# Sheet.net
KiCad netlist of a schematic drawn in Altium Designer
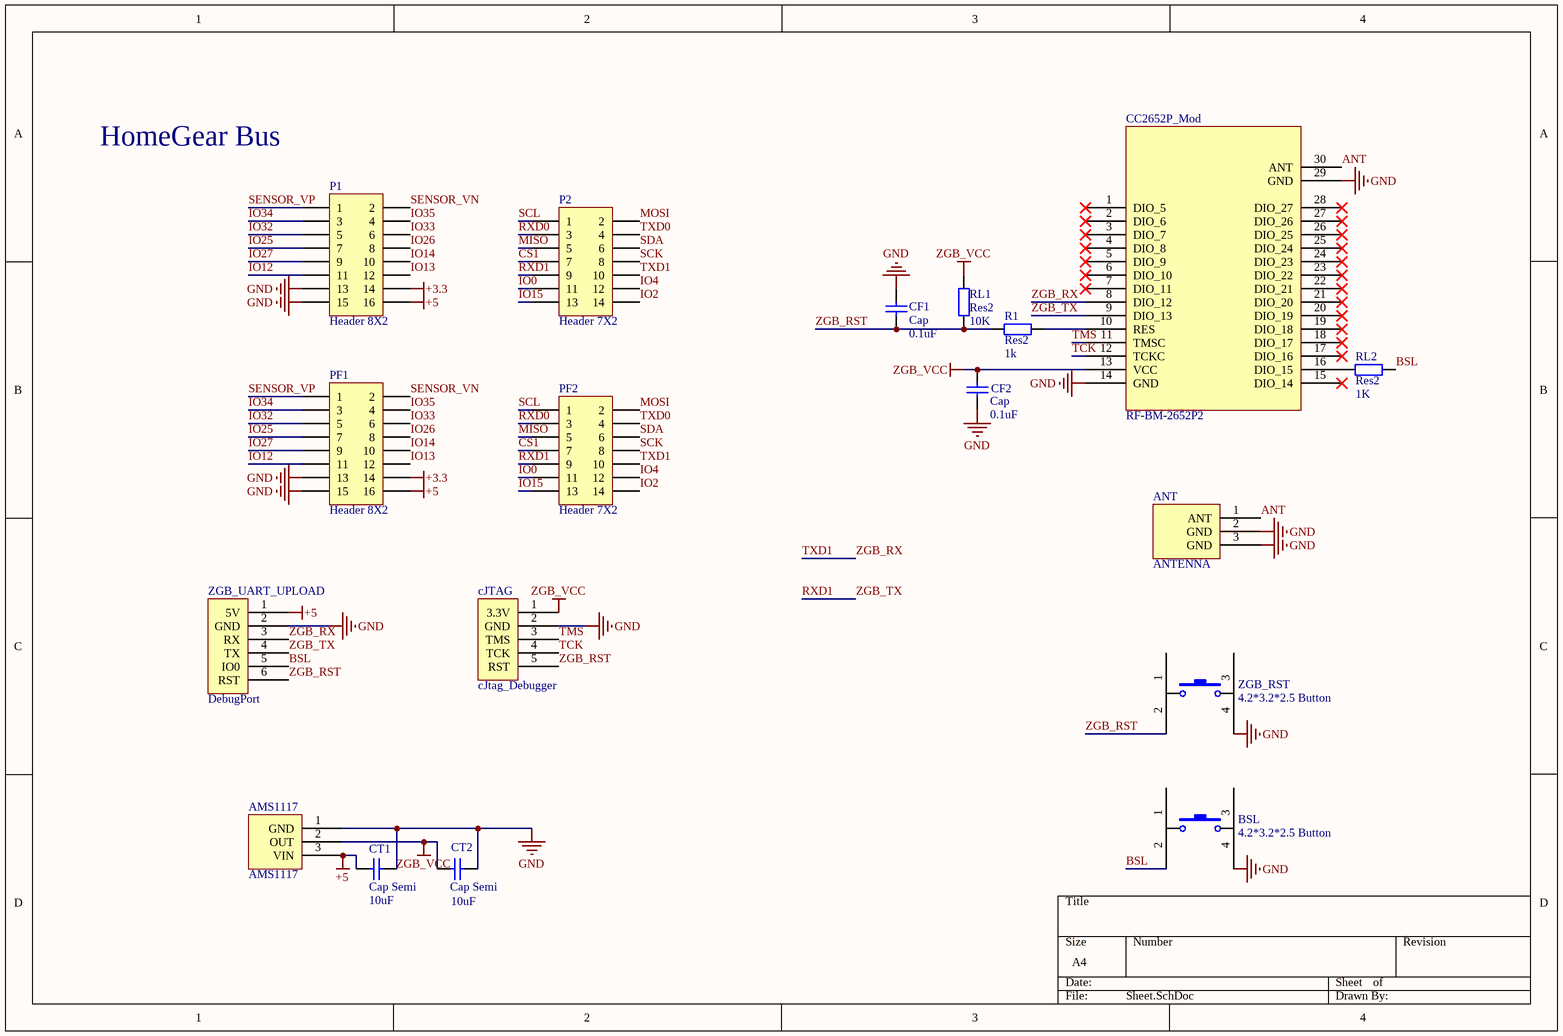
[diagram p0: Sheet.SchDoc]

(export (version "E")
  (design (tool "Eeschema 10.0.6"))
  (components
    (comp (ref "AMS1117")
      (value "AMS1117")
      (footprint "SOT-223-2")
      (libsource (lib "Schlib2") (part "AMS1117"))
    )
    (comp (ref "ANT") (value "ANTENNA") (footprint "SMA-2") (libsource (lib "我的元件库") (part "ANTENNA")))
    (comp (ref "BSL")
      (value "4.2*3.2*2.5 Button")
      (footprint "TSW 4.2*3.2*2.5")
      (libsource (lib "我的元件库") (part "4.2*3.2*2.5 Button"))
    )
    (comp (ref "CC2652P_Mod")
      (value "RF-BM-2652P2")
      (footprint "RF-BM-2652P2")
      (libsource (lib "我的元件库") (part "RF-BM-2652P2"))
    )
    (comp (ref "CF1")
      (value "Cap")
      (footprint "MY0603")
      (description "Capacitor")
      (fields (field (name "ALTIUM_VALUE") "0.1uF") (field (name "PUBLISHER") "Altium Limited"))
      (libsource (lib "Miscellaneous Devices") (part "Cap"))
    )
    (comp (ref "CF2")
      (value "Cap")
      (footprint "MY0603")
      (description "Capacitor")
      (fields (field (name "ALTIUM_VALUE") "0.1uF") (field (name "PUBLISHER") "Altium Limited"))
      (libsource (lib "Miscellaneous Devices") (part "Cap"))
    )
    (comp (ref "cJTAG")
      (value "cJtag_Debugger")
      (footprint "XH2.54-WI-5P")
      (libsource (lib "我的元件库") (part "cJtag_Debugger"))
    )
    (comp (ref "CT1")
      (value "Cap Semi")
      (footprint "My1206")
      (description "Capacitor (Semiconductor SIM Model)")
      (fields (field (name "ALTIUM_VALUE") "10uF") (field (name "PUBLISHER") "Altium Limited"))
      (libsource (lib "Miscellaneous Devices") (part "Cap Semi"))
    )
    (comp (ref "CT2")
      (value "Cap Semi")
      (footprint "My1206")
      (description "Capacitor (Semiconductor SIM Model)")
      (fields (field (name "ALTIUM_VALUE") "10uF") (field (name "PUBLISHER") "Altium Limited"))
      (libsource (lib "Miscellaneous Devices") (part "Cap Semi"))
    )
    (comp (ref "P1")
      (value "Header 8X2")
      (footprint "SMD_PIN_HDR8x2_2.0MM")
      (description "Header, 8-Pin, Dual row")
      (fields (field (name "PUBLISHER") "Altium Limited"))
      (libsource (lib "Miscellaneous Connectors") (part "Header 8X2"))
    )
    (comp (ref "P2")
      (value "Header 7X2")
      (footprint "SMD_PIN_HDR7x2_2.0MM")
      (description "Header, 7-Pin, Dual row")
      (fields (field (name "PUBLISHER") "Altium Limited"))
      (libsource (lib "Miscellaneous Connectors") (part "Header 7X2"))
    )
    (comp (ref "PF1")
      (value "Header 8X2")
      (footprint "SMD_FEM_HDR8x2_2.0MM")
      (description "Header, 8-Pin, Dual row")
      (fields (field (name "PUBLISHER") "Altium Limited"))
      (libsource (lib "Miscellaneous Connectors") (part "Header 8X2"))
    )
    (comp (ref "PF2")
      (value "Header 7X2")
      (footprint "SMD_FEM_HDR7x2_2.0MM")
      (description "Header, 7-Pin, Dual row")
      (fields (field (name "PUBLISHER") "Altium Limited"))
      (libsource (lib "Miscellaneous Connectors") (part "Header 7X2"))
    )
    (comp (ref "R1")
      (value "Res2")
      (footprint "MY0603")
      (description "Resistor")
      (fields (field (name "ALTIUM_VALUE") "1k") (field (name "PUBLISHER") "Altium Limited"))
      (libsource (lib "Miscellaneous Devices") (part "Res2"))
    )
    (comp (ref "RL1")
      (value "Res2")
      (footprint "MY0603")
      (description "Resistor")
      (fields (field (name "ALTIUM_VALUE") "10K") (field (name "PUBLISHER") "Altium Limited"))
      (libsource (lib "") (part "Res2_1"))
    )
    (comp (ref "RL2")
      (value "Res2")
      (footprint "MY0603")
      (description "Resistor")
      (fields (field (name "ALTIUM_VALUE") "1K") (field (name "PUBLISHER") "Altium Limited"))
      (libsource (lib "Miscellaneous Devices") (part "Res2"))
    )
    (comp (ref "ZGB_RST")
      (value "4.2*3.2*2.5 Button")
      (footprint "TSW 4.2*3.2*2.5")
      (libsource (lib "我的元件库") (part "4.2*3.2*2.5 Button"))
    )
    (comp (ref "ZGB_UART_UPLOAD")
      (value "DebugPort")
      (footprint "XH2.54-WI-6P")
      (libsource (lib "ESP12_BME280_OLED_IR") (part "DebugPort"))
    )
  )
  (nets
    (net (code "1") (name "+3.3") (class "Default")
      (node (ref "P1") (pin "14") (pinfunction "14_14") (pintype "passive"))
      (node (ref "PF1") (pin "14") (pinfunction "14_14") (pintype "passive"))
    )
    (net (code "2") (name "+5") (class "Default")
      (node (ref "AMS1117") (pin "3") (pinfunction "VIN_3") (pintype "passive"))
      (node (ref "CT1") (pin "1") (pinfunction "1_1") (pintype "passive"))
      (node (ref "P1") (pin "16") (pinfunction "16_16") (pintype "passive"))
      (node (ref "PF1") (pin "16") (pinfunction "16_16") (pintype "passive"))
      (node (ref "ZGB_UART_UPLOAD") (pin "1") (pinfunction "5V_1") (pintype "passive"))
    )
    (net (code "4") (name "/ANT") (class "Default")
      (node (ref "ANT") (pin "1") (pinfunction "ANT_1") (pintype "passive"))
      (node (ref "CC2652P_Mod") (pin "30") (pinfunction "ANT_30") (pintype "passive"))
    )
    (net (code "5") (name "/BSL") (class "Default")
      (node (ref "BSL") (pin "2") (pinfunction "2_2") (pintype "passive"))
      (node (ref "RL2") (pin "2") (pinfunction "2_2") (pintype "passive"))
      (node (ref "ZGB_UART_UPLOAD") (pin "5") (pinfunction "IO0_5") (pintype "passive"))
    )
    (net (code "6") (name "/CS1") (class "Default")
      (node (ref "P2") (pin "7") (pinfunction "7_7") (pintype "passive"))
      (node (ref "PF2") (pin "7") (pinfunction "7_7") (pintype "passive"))
    )
    (net (code "7") (name "/IO0") (class "Default")
      (node (ref "P2") (pin "11") (pinfunction "11_11") (pintype "passive"))
      (node (ref "PF2") (pin "11") (pinfunction "11_11") (pintype "passive"))
    )
    (net (code "8") (name "/IO2") (class "Default")
      (node (ref "P2") (pin "14") (pinfunction "14_14") (pintype "passive"))
      (node (ref "PF2") (pin "14") (pinfunction "14_14") (pintype "passive"))
    )
    (net (code "9") (name "/IO4") (class "Default")
      (node (ref "P2") (pin "12") (pinfunction "12_12") (pintype "passive"))
      (node (ref "PF2") (pin "12") (pinfunction "12_12") (pintype "passive"))
    )
    (net (code "10") (name "/IO12") (class "Default")
      (node (ref "P1") (pin "11") (pinfunction "11_11") (pintype "passive"))
      (node (ref "PF1") (pin "11") (pinfunction "11_11") (pintype "passive"))
    )
    (net (code "11") (name "/IO13") (class "Default")
      (node (ref "P1") (pin "12") (pinfunction "12_12") (pintype "passive"))
      (node (ref "PF1") (pin "12") (pinfunction "12_12") (pintype "passive"))
    )
    (net (code "12") (name "/IO14") (class "Default")
      (node (ref "P1") (pin "10") (pinfunction "10_10") (pintype "passive"))
      (node (ref "PF1") (pin "10") (pinfunction "10_10") (pintype "passive"))
    )
    (net (code "13") (name "/IO15") (class "Default")
      (node (ref "P2") (pin "13") (pinfunction "13_13") (pintype "passive"))
      (node (ref "PF2") (pin "13") (pinfunction "13_13") (pintype "passive"))
    )
    (net (code "14") (name "/IO25") (class "Default")
      (node (ref "P1") (pin "7") (pinfunction "7_7") (pintype "passive"))
      (node (ref "PF1") (pin "7") (pinfunction "7_7") (pintype "passive"))
    )
    (net (code "15") (name "/IO26") (class "Default")
      (node (ref "P1") (pin "8") (pinfunction "8_8") (pintype "passive"))
      (node (ref "PF1") (pin "8") (pinfunction "8_8") (pintype "passive"))
    )
    (net (code "16") (name "/IO27") (class "Default")
      (node (ref "P1") (pin "9") (pinfunction "9_9") (pintype "passive"))
      (node (ref "PF1") (pin "9") (pinfunction "9_9") (pintype "passive"))
    )
    (net (code "17") (name "/IO32") (class "Default")
      (node (ref "P1") (pin "5") (pinfunction "5_5") (pintype "passive"))
      (node (ref "PF1") (pin "5") (pinfunction "5_5") (pintype "passive"))
    )
    (net (code "18") (name "/IO33") (class "Default")
      (node (ref "P1") (pin "6") (pinfunction "6_6") (pintype "passive"))
      (node (ref "PF1") (pin "6") (pinfunction "6_6") (pintype "passive"))
    )
    (net (code "19") (name "/IO34") (class "Default")
      (node (ref "P1") (pin "3") (pinfunction "3_3") (pintype "passive"))
      (node (ref "PF1") (pin "3") (pinfunction "3_3") (pintype "passive"))
    )
    (net (code "20") (name "/IO35") (class "Default")
      (node (ref "P1") (pin "4") (pinfunction "4_4") (pintype "passive"))
      (node (ref "PF1") (pin "4") (pinfunction "4_4") (pintype "passive"))
    )
    (net (code "21") (name "/MISO") (class "Default")
      (node (ref "P2") (pin "5") (pinfunction "5_5") (pintype "passive"))
      (node (ref "PF2") (pin "5") (pinfunction "5_5") (pintype "passive"))
    )
    (net (code "22") (name "/MOSI") (class "Default")
      (node (ref "P2") (pin "2") (pinfunction "2_2") (pintype "passive"))
      (node (ref "PF2") (pin "2") (pinfunction "2_2") (pintype "passive"))
    )
    (net (code "23") (name "/RXD0") (class "Default")
      (node (ref "P2") (pin "3") (pinfunction "3_3") (pintype "passive"))
      (node (ref "PF2") (pin "3") (pinfunction "3_3") (pintype "passive"))
    )
    (net (code "24") (name "/RXD1") (class "Default")
      (node (ref "CC2652P_Mod") (pin "9") (pinfunction "DIO_13_9") (pintype "passive"))
      (node (ref "P2") (pin "9") (pinfunction "9_9") (pintype "passive"))
      (node (ref "PF2") (pin "9") (pinfunction "9_9") (pintype "passive"))
      (node (ref "ZGB_UART_UPLOAD") (pin "4") (pinfunction "TX_4") (pintype "passive"))
    )
    (net (code "25") (name "/SCK") (class "Default")
      (node (ref "P2") (pin "8") (pinfunction "8_8") (pintype "passive"))
      (node (ref "PF2") (pin "8") (pinfunction "8_8") (pintype "passive"))
    )
    (net (code "26") (name "/SCL") (class "Default")
      (node (ref "P2") (pin "1") (pinfunction "1_1") (pintype "passive"))
      (node (ref "PF2") (pin "1") (pinfunction "1_1") (pintype "passive"))
    )
    (net (code "27") (name "/SDA") (class "Default")
      (node (ref "P2") (pin "6") (pinfunction "6_6") (pintype "passive"))
      (node (ref "PF2") (pin "6") (pinfunction "6_6") (pintype "passive"))
    )
    (net (code "28") (name "/SENSOR_VN") (class "Default")
      (node (ref "P1") (pin "2") (pinfunction "2_2") (pintype "passive"))
      (node (ref "PF1") (pin "2") (pinfunction "2_2") (pintype "passive"))
    )
    (net (code "29") (name "/SENSOR_VP") (class "Default")
      (node (ref "P1") (pin "1") (pinfunction "1_1") (pintype "passive"))
      (node (ref "PF1") (pin "1") (pinfunction "1_1") (pintype "passive"))
    )
    (net (code "30") (name "/TCK") (class "Default")
      (node (ref "CC2652P_Mod") (pin "12") (pinfunction "TCKC_12") (pintype "passive"))
      (node (ref "cJTAG") (pin "4") (pinfunction "TCK_4") (pintype "passive"))
    )
    (net (code "31") (name "/TMS") (class "Default")
      (node (ref "CC2652P_Mod") (pin "11") (pinfunction "TMSC_11") (pintype "passive"))
      (node (ref "cJTAG") (pin "3") (pinfunction "TMS_3") (pintype "passive"))
    )
    (net (code "32") (name "/TXD0") (class "Default")
      (node (ref "P2") (pin "4") (pinfunction "4_4") (pintype "passive"))
      (node (ref "PF2") (pin "4") (pinfunction "4_4") (pintype "passive"))
    )
    (net (code "33") (name "/TXD1") (class "Default")
      (node (ref "CC2652P_Mod") (pin "8") (pinfunction "DIO_12_8") (pintype "passive"))
      (node (ref "P2") (pin "10") (pinfunction "10_10") (pintype "passive"))
      (node (ref "PF2") (pin "10") (pinfunction "10_10") (pintype "passive"))
      (node (ref "ZGB_UART_UPLOAD") (pin "3") (pinfunction "RX_3") (pintype "passive"))
    )
    (net (code "34") (name "/ZGB_RST") (class "Default")
      (node (ref "CF1") (pin "2") (pinfunction "2_2") (pintype "passive"))
      (node (ref "R1") (pin "1") (pinfunction "1_1") (pintype "passive"))
      (node (ref "RL1") (pin "1") (pinfunction "1_1") (pintype "passive"))
      (node (ref "ZGB_RST") (pin "2") (pinfunction "2_2") (pintype "passive"))
      (node (ref "ZGB_UART_UPLOAD") (pin "6") (pinfunction "RST_6") (pintype "passive"))
      (node (ref "cJTAG") (pin "5") (pinfunction "RST_5") (pintype "passive"))
    )
    (net (code "35") (name "GND") (class "Default")
      (node (ref "AMS1117") (pin "1") (pinfunction "GND_1") (pintype "passive"))
      (node (ref "ANT") (pin "2") (pinfunction "GND_2") (pintype "passive"))
      (node (ref "ANT") (pin "3") (pinfunction "GND_3") (pintype "passive"))
      (node (ref "BSL") (pin "4") (pinfunction "4_4") (pintype "passive"))
      (node (ref "CC2652P_Mod") (pin "14") (pinfunction "GND_14") (pintype "passive"))
      (node (ref "CC2652P_Mod") (pin "29") (pinfunction "GND_29") (pintype "passive"))
      (node (ref "CF1") (pin "1") (pinfunction "1_1") (pintype "passive"))
      (node (ref "CF2") (pin "1") (pinfunction "1_1") (pintype "passive"))
      (node (ref "CT1") (pin "2") (pinfunction "2_2") (pintype "passive"))
      (node (ref "CT2") (pin "2") (pinfunction "2_2") (pintype "passive"))
      (node (ref "P1") (pin "13") (pinfunction "13_13") (pintype "passive"))
      (node (ref "P1") (pin "15") (pinfunction "15_15") (pintype "passive"))
      (node (ref "PF1") (pin "13") (pinfunction "13_13") (pintype "passive"))
      (node (ref "PF1") (pin "15") (pinfunction "15_15") (pintype "passive"))
      (node (ref "ZGB_RST") (pin "4") (pinfunction "4_4") (pintype "passive"))
      (node (ref "ZGB_UART_UPLOAD") (pin "2") (pinfunction "GND_2") (pintype "passive"))
      (node (ref "cJTAG") (pin "2") (pinfunction "GND_2") (pintype "passive"))
    )
    (net (code "36") (name "Net-(CC2652P_Mod-DIO_15)") (class "Default")
      (node (ref "CC2652P_Mod") (pin "16") (pinfunction "DIO_15_16") (pintype "passive"))
      (node (ref "RL2") (pin "1") (pinfunction "1_1") (pintype "passive"))
    )
    (net (code "37") (name "Net-(CC2652P_Mod-RES)") (class "Default")
      (node (ref "CC2652P_Mod") (pin "10") (pinfunction "RES_10") (pintype "passive"))
      (node (ref "R1") (pin "2") (pinfunction "2_2") (pintype "passive"))
    )
    (net (code "38") (name "ZGB_VCC") (class "Default")
      (node (ref "AMS1117") (pin "2") (pinfunction "OUT_2") (pintype "passive"))
      (node (ref "CC2652P_Mod") (pin "13") (pinfunction "VCC_13") (pintype "passive"))
      (node (ref "CF2") (pin "2") (pinfunction "2_2") (pintype "passive"))
      (node (ref "CT2") (pin "1") (pinfunction "1_1") (pintype "passive"))
      (node (ref "RL1") (pin "2") (pinfunction "2_2") (pintype "passive"))
      (node (ref "cJTAG") (pin "1") (pinfunction "3.3V_1") (pintype "passive"))
    )
    (net (code "39") (name "unconnected-(BSL-Pad1)") (class "Default")
      (node (ref "BSL") (pin "1") (pinfunction "1_1") (pintype "passive"))
    )
    (net (code "40") (name "unconnected-(BSL-Pad3)") (class "Default")
      (node (ref "BSL") (pin "3") (pinfunction "3_3") (pintype "passive"))
    )
    (net (code "41") (name "unconnected-(CC2652P_Mod-DIO_5-Pad1)") (class "Default")
      (node (ref "CC2652P_Mod") (pin "1") (pinfunction "DIO_5_1") (pintype "passive+no_connect"))
    )
    (net (code "42") (name "unconnected-(CC2652P_Mod-DIO_6-Pad2)") (class "Default")
      (node (ref "CC2652P_Mod") (pin "2") (pinfunction "DIO_6_2") (pintype "passive+no_connect"))
    )
    (net (code "43") (name "unconnected-(CC2652P_Mod-DIO_7-Pad3)") (class "Default")
      (node (ref "CC2652P_Mod") (pin "3") (pinfunction "DIO_7_3") (pintype "passive+no_connect"))
    )
    (net (code "44") (name "unconnected-(CC2652P_Mod-DIO_8-Pad4)") (class "Default")
      (node (ref "CC2652P_Mod") (pin "4") (pinfunction "DIO_8_4") (pintype "passive+no_connect"))
    )
    (net (code "45") (name "unconnected-(CC2652P_Mod-DIO_9-Pad5)") (class "Default")
      (node (ref "CC2652P_Mod") (pin "5") (pinfunction "DIO_9_5") (pintype "passive+no_connect"))
    )
    (net (code "46") (name "unconnected-(CC2652P_Mod-DIO_10-Pad6)") (class "Default")
      (node (ref "CC2652P_Mod") (pin "6") (pinfunction "DIO_10_6") (pintype "passive+no_connect"))
    )
    (net (code "47") (name "unconnected-(CC2652P_Mod-DIO_11-Pad7)") (class "Default")
      (node (ref "CC2652P_Mod") (pin "7") (pinfunction "DIO_11_7") (pintype "passive+no_connect"))
    )
    (net (code "48") (name "unconnected-(CC2652P_Mod-DIO_14-Pad15)") (class "Default")
      (node (ref "CC2652P_Mod") (pin "15") (pinfunction "DIO_14_15") (pintype "passive+no_connect"))
    )
    (net (code "49") (name "unconnected-(CC2652P_Mod-DIO_16-Pad17)") (class "Default")
      (node (ref "CC2652P_Mod") (pin "17") (pinfunction "DIO_16_17") (pintype "passive+no_connect"))
    )
    (net (code "50") (name "unconnected-(CC2652P_Mod-DIO_17-Pad18)") (class "Default")
      (node (ref "CC2652P_Mod") (pin "18") (pinfunction "DIO_17_18") (pintype "passive+no_connect"))
    )
    (net (code "51") (name "unconnected-(CC2652P_Mod-DIO_18-Pad19)") (class "Default")
      (node (ref "CC2652P_Mod") (pin "19") (pinfunction "DIO_18_19") (pintype "passive+no_connect"))
    )
    (net (code "52") (name "unconnected-(CC2652P_Mod-DIO_19-Pad20)") (class "Default")
      (node (ref "CC2652P_Mod") (pin "20") (pinfunction "DIO_19_20") (pintype "passive+no_connect"))
    )
    (net (code "53") (name "unconnected-(CC2652P_Mod-DIO_20-Pad21)") (class "Default")
      (node (ref "CC2652P_Mod") (pin "21") (pinfunction "DIO_20_21") (pintype "passive+no_connect"))
    )
    (net (code "54") (name "unconnected-(CC2652P_Mod-DIO_21-Pad22)") (class "Default")
      (node (ref "CC2652P_Mod") (pin "22") (pinfunction "DIO_21_22") (pintype "passive+no_connect"))
    )
    (net (code "55") (name "unconnected-(CC2652P_Mod-DIO_22-Pad23)") (class "Default")
      (node (ref "CC2652P_Mod") (pin "23") (pinfunction "DIO_22_23") (pintype "passive+no_connect"))
    )
    (net (code "56") (name "unconnected-(CC2652P_Mod-DIO_23-Pad24)") (class "Default")
      (node (ref "CC2652P_Mod") (pin "24") (pinfunction "DIO_23_24") (pintype "passive+no_connect"))
    )
    (net (code "57") (name "unconnected-(CC2652P_Mod-DIO_24-Pad25)") (class "Default")
      (node (ref "CC2652P_Mod") (pin "25") (pinfunction "DIO_24_25") (pintype "passive+no_connect"))
    )
    (net (code "58") (name "unconnected-(CC2652P_Mod-DIO_25-Pad26)") (class "Default")
      (node (ref "CC2652P_Mod") (pin "26") (pinfunction "DIO_25_26") (pintype "passive+no_connect"))
    )
    (net (code "59") (name "unconnected-(CC2652P_Mod-DIO_26-Pad27)") (class "Default")
      (node (ref "CC2652P_Mod") (pin "27") (pinfunction "DIO_26_27") (pintype "passive+no_connect"))
    )
    (net (code "60") (name "unconnected-(CC2652P_Mod-DIO_27-Pad28)") (class "Default")
      (node (ref "CC2652P_Mod") (pin "28") (pinfunction "DIO_27_28") (pintype "passive+no_connect"))
    )
    (net (code "61") (name "unconnected-(ZGB_RST-Pad1)") (class "Default")
      (node (ref "ZGB_RST") (pin "1") (pinfunction "1_1") (pintype "passive"))
    )
    (net (code "62") (name "unconnected-(ZGB_RST-Pad3)") (class "Default")
      (node (ref "ZGB_RST") (pin "3") (pinfunction "3_3") (pintype "passive"))
    )
  )
)
